# MCLR.net
KiCad netlist of a schematic drawn in Altium Designer
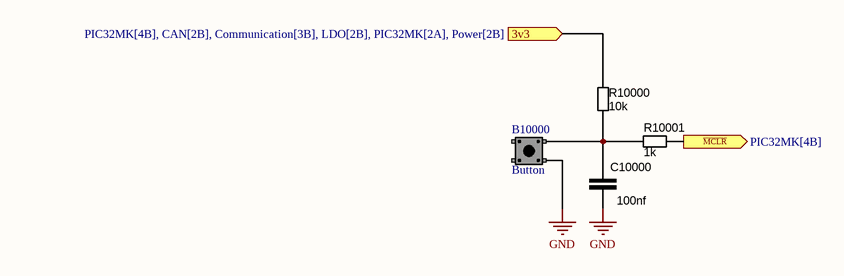
[diagram p0: MCLR.SchDoc]

(export (version "E")
  (design (tool "Eeschema 10.0.6"))
  (components
    (comp (ref "B10000")
      (value "Button")
      (footprint "ElectroMechanical2:ButtonSMD")
      (description "4 Pin Button")
      (libsource (lib "ElectroMechanical2") (part "Button"))
    )
    (comp (ref "C10000")
      (value "100nf")
      (footprint "CAP_0603")
      (description "CAP CER 100nF 0603 25V X7R")
      (libsource (lib "CapacitorsIntegrated") (part "C000007"))
    )
    (comp (ref "R10000")
      (value "10k")
      (footprint "RES_0603")
      (description "RES 100K OHM 1% 1/10W 0603")
      (libsource (lib "") (part "R000006_1"))
    )
    (comp (ref "R10001")
      (value "1k")
      (footprint "RES_0603")
      (description "RES 100K OHM 1% 1/10W 0603")
      (libsource (lib "ResistorsIntegrated") (part "R000006"))
    )
  )
  (nets
    (net (code "1") (name "/3v3") (class "Default")
      (node (ref "R10000") (pin "2") (pinfunction "2_2") (pintype "passive"))
    )
    (net (code "2") (name "/~{MCLR}") (class "Default")
      (node (ref "R10001") (pin "1") (pinfunction "1_1") (pintype "passive"))
    )
    (net (code "3") (name "GND") (class "Default")
      (node (ref "B10000") (pin "2") (pinfunction "2_2") (pintype "passive"))
      (node (ref "C10000") (pin "1") (pinfunction "1_1") (pintype "passive"))
    )
    (net (code "4") (name "Net-(B10000-Pad1)") (class "Default")
      (node (ref "B10000") (pin "1") (pinfunction "1_1") (pintype "passive"))
      (node (ref "C10000") (pin "2") (pinfunction "2_2") (pintype "passive"))
      (node (ref "R10000") (pin "1") (pinfunction "1_1") (pintype "passive"))
      (node (ref "R10001") (pin "2") (pinfunction "2_2") (pintype "passive"))
    )
  )
)
